# SoilMoistureSensor.net
KiCad netlist of a schematic drawn in Altium Designer
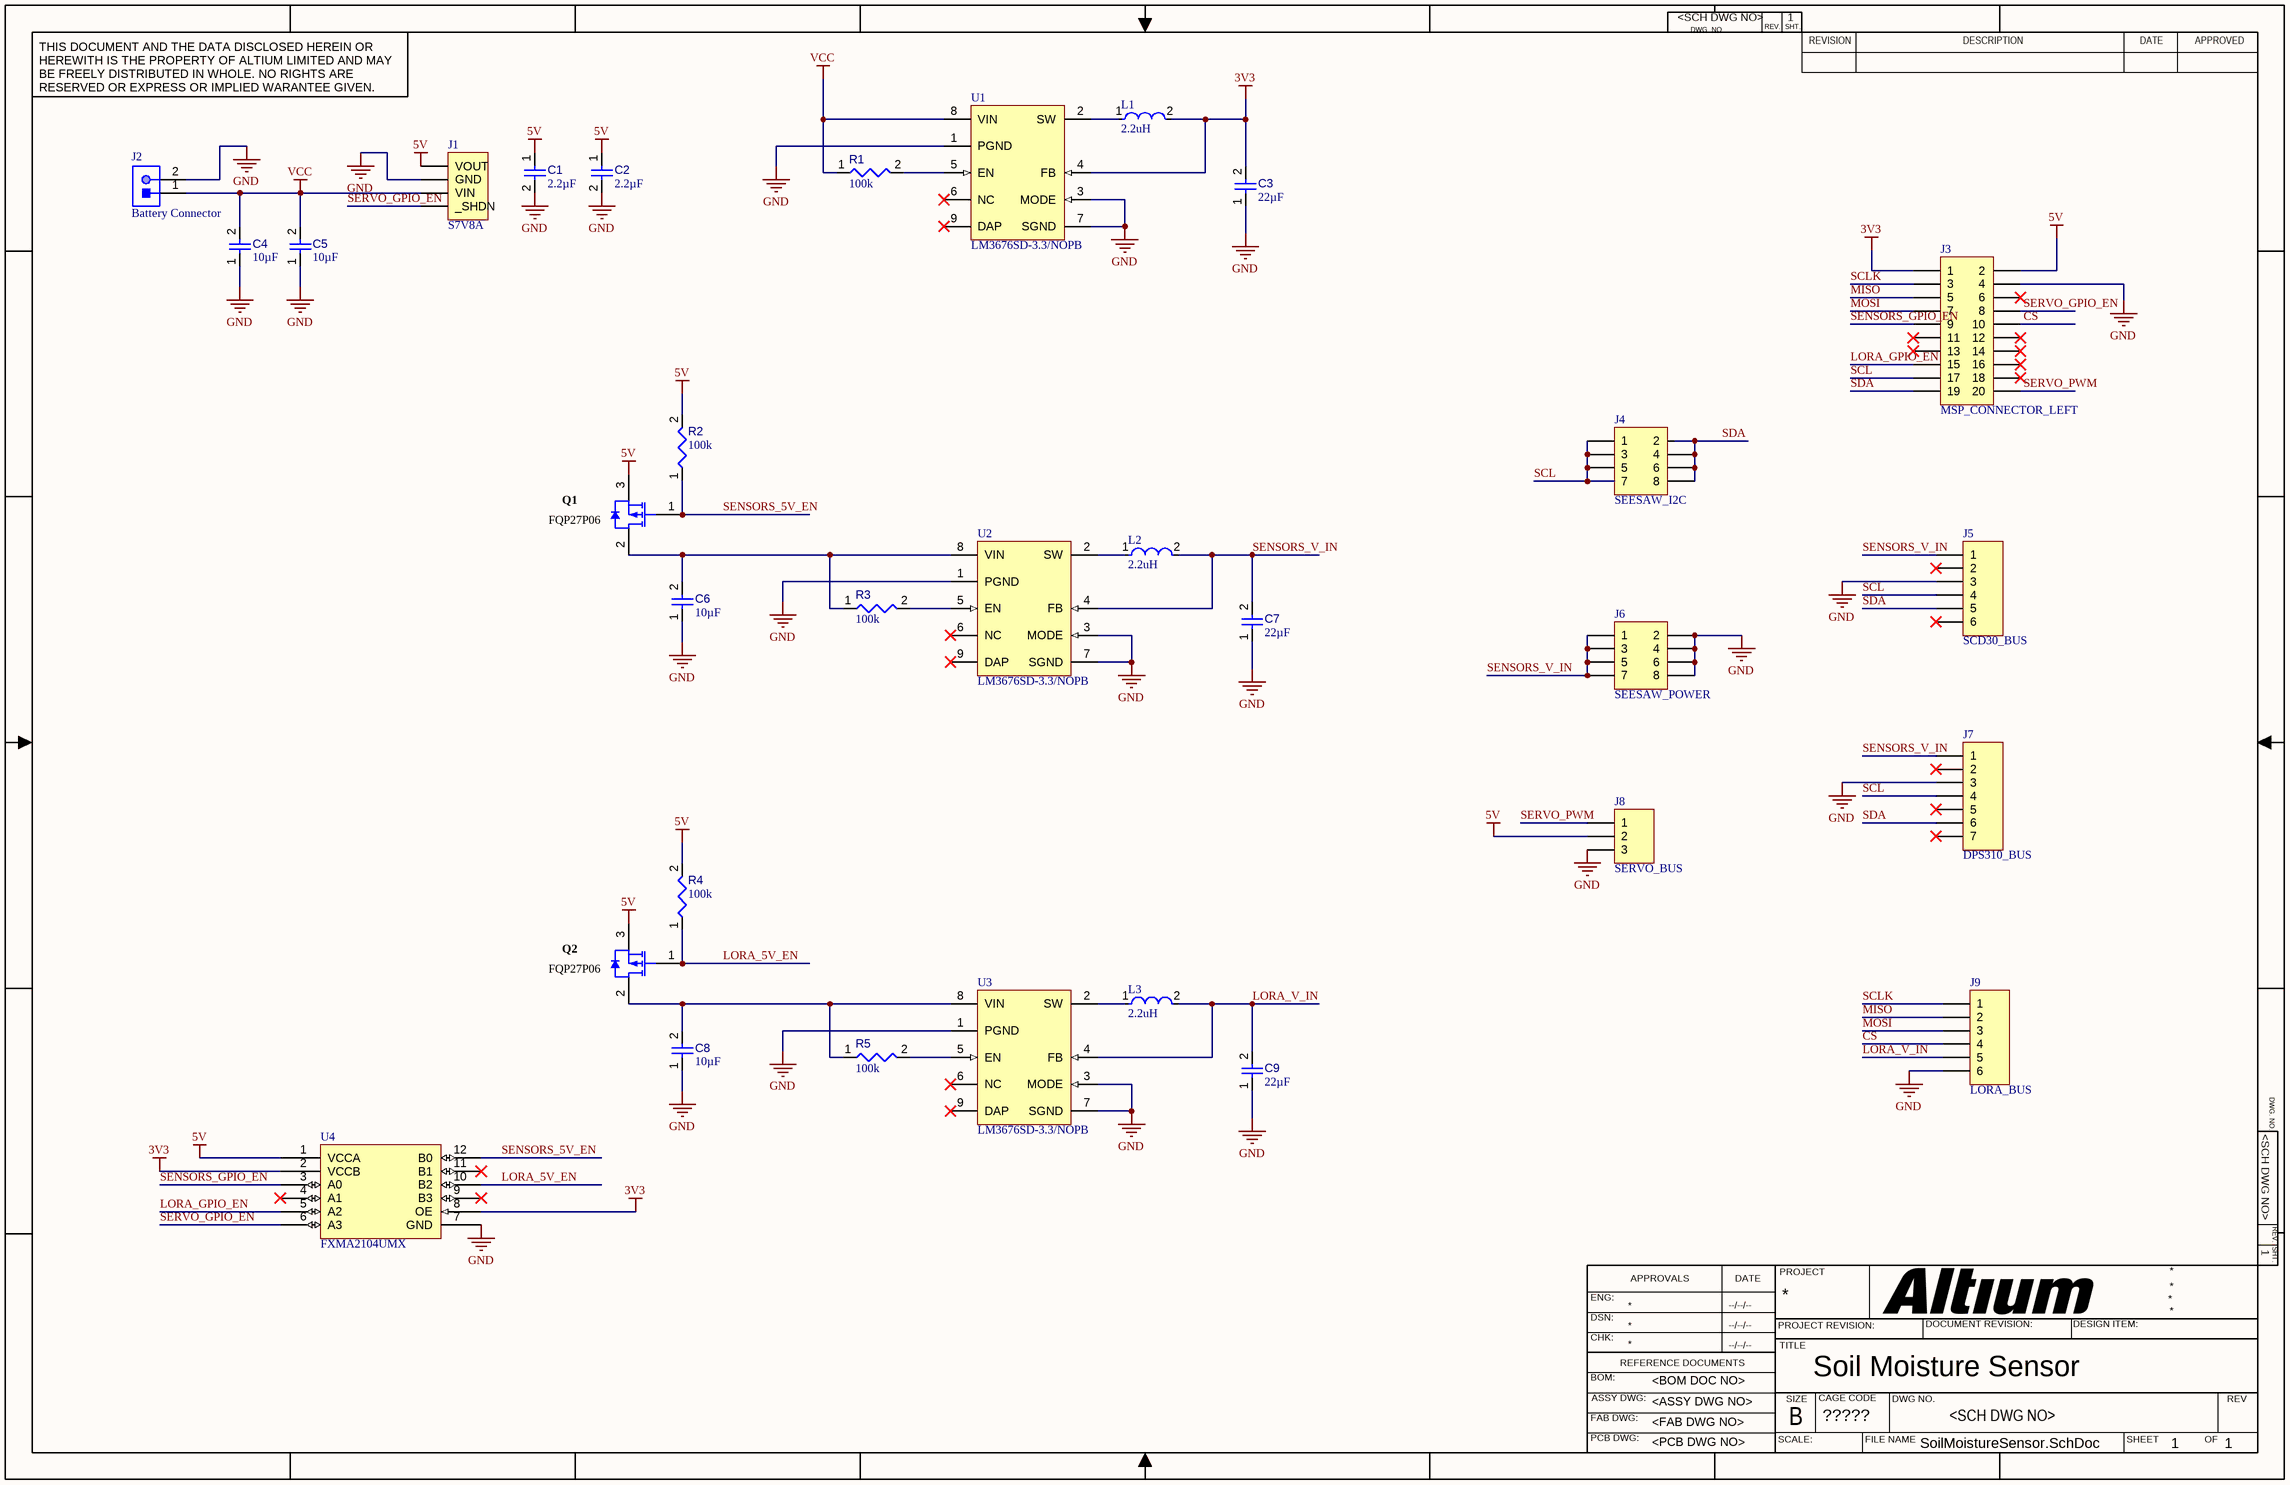
[diagram p0: SoilMoistureSensor.SchDoc]

(export (version "E")
  (design (tool "Eeschema 10.0.6"))
  (components
    (comp (ref "C1")
      (value "2.2µF")
      (footprint "CAPC0402(1005)60_L")
      (description "Chip Capacitor, 2,2µF +/-20%, 10V, 0402, Thickness 0.6 mm")
      (fields (field (name "TOLERANCE") "10%") (field (name "Comment") "Capacitor 2,2µF +/-20% 10V 0402"))
      (libsource (lib "University of Wisconsin-Madison CAE") (part "CAP-NP-2"))
    )
    (comp (ref "C2")
      (value "2.2µF")
      (footprint "CAPC0402(1005)60_L")
      (description "Chip Capacitor, 2,2µF +/-20%, 10V, 0402, Thickness 0.6 mm")
      (fields (field (name "TOLERANCE") "10%") (field (name "Comment") "Capacitor 2,2µF +/-20% 10V 0402"))
      (libsource (lib "University of Wisconsin-Madison CAE") (part "CAP-NP-2"))
    )
    (comp (ref "C3")
      (value "22µF")
      (footprint "CAPC0805(2012)145_L")
      (description "Chip Capacitor, 22µF +/-40%, 16V, 0805, Thickness 1.45 mm")
      (fields (field (name "TOLERANCE") "5%") (field (name "Comment") "Capacitor 22µF +/-40% 16V 0805"))
      (libsource (lib "University of Wisconsin-Madison CAE") (part "CAP-NP-2"))
    )
    (comp (ref "C4")
      (value "10µF")
      (footprint "CAPC0805(2012)145_L")
      (description "Chip Capacitor, 10µF +/-20%, 25V, 0805, Thickness 1.45 mm")
      (fields (field (name "TOLERANCE") "10%") (field (name "Comment") "Capacitor 10µF +/-20% 25V 0805"))
      (libsource (lib "University of Wisconsin-Madison CAE") (part "CAP-NP-2"))
    )
    (comp (ref "C5")
      (value "10µF")
      (footprint "CAPC0805(2012)145_L")
      (description "Chip Capacitor, 10µF +/-20%, 25V, 0805, Thickness 1.45 mm")
      (fields (field (name "TOLERANCE") "10%") (field (name "Comment") "Capacitor 10µF +/-20% 25V 0805"))
      (libsource (lib "University of Wisconsin-Madison CAE") (part "CAP-NP-2"))
    )
    (comp (ref "C6")
      (value "10µF")
      (footprint "CAPC0805(2012)145_L")
      (description "Chip Capacitor, 10µF +/-20%, 25V, 0805, Thickness 1.45 mm")
      (fields (field (name "TOLERANCE") "10%") (field (name "Comment") "Capacitor 10µF +/-20% 25V 0805"))
      (libsource (lib "University of Wisconsin-Madison CAE") (part "CAP-NP-2"))
    )
    (comp (ref "C7")
      (value "22µF")
      (footprint "CAPC0805(2012)145_L")
      (description "Chip Capacitor, 22µF +/-40%, 16V, 0805, Thickness 1.45 mm")
      (fields (field (name "TOLERANCE") "5%") (field (name "Comment") "Capacitor 22µF +/-40% 16V 0805"))
      (libsource (lib "University of Wisconsin-Madison CAE") (part "CAP-NP-2"))
    )
    (comp (ref "C8")
      (value "10µF")
      (footprint "CAPC0805(2012)145_L")
      (description "Chip Capacitor, 10µF +/-20%, 25V, 0805, Thickness 1.45 mm")
      (fields (field (name "TOLERANCE") "10%") (field (name "Comment") "Capacitor 10µF +/-20% 25V 0805"))
      (libsource (lib "University of Wisconsin-Madison CAE") (part "CAP-NP-2"))
    )
    (comp (ref "C9")
      (value "22µF")
      (footprint "CAPC0805(2012)145_L")
      (description "Chip Capacitor, 22µF +/-40%, 16V, 0805, Thickness 1.45 mm")
      (fields (field (name "TOLERANCE") "5%") (field (name "Comment") "Capacitor 22µF +/-40% 16V 0805"))
      (libsource (lib "University of Wisconsin-Madison CAE") (part "CAP-NP-2"))
    )
    (comp (ref "J1")
      (value "S7V8A")
      (footprint "HDR1X4")
      (description "Header, 4-Pin")
      (fields (field (name "PUBLISHER") "Altium Limited"))
      (libsource (lib "Miscellaneous Connectors") (part "Header 4"))
    )
    (comp (ref "J2")
      (value "Battery Connector")
      (footprint "JST-S2B-PH-K-S_V")
      (fields (field (name "MANUFACTURER") "Japan Solderless Terminals"))
      (libsource (lib "University of Wisconsin-Madison CAE") (part "CN-1P-M-R2"))
    )
    (comp (ref "J3")
      (value "MSP_CONNECTOR_LEFT")
      (footprint "HDR2X10")
      (description "Header, 10-Pin, Dual row")
      (fields (field (name "PUBLISHER") "Altium Limited"))
      (libsource (lib "Miscellaneous Connectors") (part "Header 10X2"))
    )
    (comp (ref "J4")
      (value "SEESAW_I2C")
      (footprint "HDR2X4")
      (description "Header, 4-Pin, Dual row")
      (fields (field (name "PUBLISHER") "Altium Limited"))
      (libsource (lib "Miscellaneous Connectors") (part "Header 4X2"))
    )
    (comp (ref "J5")
      (value "SCD30_BUS")
      (footprint "HDR1X6")
      (description "Header, 6-Pin")
      (fields (field (name "PUBLISHER") "Altium Limited"))
      (libsource (lib "Miscellaneous Connectors") (part "Header 6"))
    )
    (comp (ref "J6")
      (value "SEESAW_POWER")
      (footprint "HDR2X4")
      (description "Header, 4-Pin, Dual row")
      (fields (field (name "PUBLISHER") "Altium Limited"))
      (libsource (lib "Miscellaneous Connectors") (part "Header 4X2"))
    )
    (comp (ref "J7")
      (value "DPS310_BUS")
      (footprint "HDR1X7")
      (description "Header, 7-Pin")
      (fields (field (name "PUBLISHER") "Altium Limited"))
      (libsource (lib "Miscellaneous Connectors") (part "Header 7"))
    )
    (comp (ref "J8")
      (value "SERVO_BUS")
      (footprint "HDR1X3")
      (description "Header, 3-Pin")
      (fields (field (name "PUBLISHER") "Altium Limited"))
      (libsource (lib "Miscellaneous Connectors") (part "Header 3"))
    )
    (comp (ref "J9")
      (value "LORA_BUS")
      (footprint "HDR1X6")
      (description "Header, 6-Pin")
      (fields (field (name "PUBLISHER") "Altium Limited"))
      (libsource (lib "Miscellaneous Connectors") (part "Header 6"))
    )
    (comp (ref "L1")
      (value "2.2uH")
      (footprint "FP-NRH2412-MFG")
      (description "Shielded Wirewound Inductor 2.2uH 20% 1.19A 0.168Ω SMD")
      (fields (field (name "TOLERANCE") "20%"))
      (libsource (lib "Altium Content Vault") (part "725321dda6339637d4d059423bc1c3c"))
    )
    (comp (ref "L2")
      (value "2.2uH")
      (footprint "FP-NRH2412-MFG")
      (description "Shielded Wirewound Inductor 2.2uH 20% 1.19A 0.168Ω SMD")
      (fields (field (name "TOLERANCE") "20%"))
      (libsource (lib "Altium Content Vault") (part "725321dda6339637d4d059423bc1c3c"))
    )
    (comp (ref "L3")
      (value "2.2uH")
      (footprint "FP-NRH2412-MFG")
      (description "Shielded Wirewound Inductor 2.2uH 20% 1.19A 0.168Ω SMD")
      (fields (field (name "TOLERANCE") "20%"))
      (libsource (lib "Altium Content Vault") (part "725321dda6339637d4d059423bc1c3c"))
    )
    (comp (ref "Q1")
      (value "FQP27P06")
      (footprint "FAIR-TO-220-3")
      (description "P-Channel QFET(R) MOSFET, -60 V, -27 A, -55 to 175 degC, 3-Pin TO-220, RoHS, Tube")
      (fields (field (name "MANUFACTURER") "Fairchild"))
      (libsource (lib "Altium Content Vault") (part "PEMOS-GDS-3"))
    )
    (comp (ref "Q2")
      (value "FQP27P06")
      (footprint "FAIR-TO-220-3")
      (description "P-Channel QFET(R) MOSFET, -60 V, -27 A, -55 to 175 degC, 3-Pin TO-220, RoHS, Tube")
      (fields (field (name "MANUFACTURER") "Fairchild"))
      (libsource (lib "Altium Content Vault") (part "PEMOS-GDS-3"))
    )
    (comp (ref "R1")
      (value "100k")
      (footprint "RESC2013X70X40ML20T20")
      (description "Chip Resistor, 100 KOhm, +/- 1%, 0.125 W, -55 to 155 degC, 0805 (2012 Metric)")
      (fields (field (name "POWER") "125mW") (field (name "TOLERANCE") "1%"))
      (libsource (lib "University of Wisconsin-Madison CAE") (part "RES-2"))
    )
    (comp (ref "R2")
      (value "100k")
      (footprint "RESC2013X70X40ML20T20")
      (description "Chip Resistor, 100 KOhm, +/- 1%, 0.125 W, -55 to 155 degC, 0805 (2012 Metric)")
      (fields (field (name "POWER") "125mW") (field (name "TOLERANCE") "1%"))
      (libsource (lib "University of Wisconsin-Madison CAE") (part "RES-2"))
    )
    (comp (ref "R3")
      (value "100k")
      (footprint "RESC2013X70X40ML20T20")
      (description "Chip Resistor, 100 KOhm, +/- 1%, 0.125 W, -55 to 155 degC, 0805 (2012 Metric)")
      (fields (field (name "POWER") "125mW") (field (name "TOLERANCE") "1%"))
      (libsource (lib "University of Wisconsin-Madison CAE") (part "RES-2"))
    )
    (comp (ref "R4")
      (value "100k")
      (footprint "RESC2013X70X40ML20T20")
      (description "Chip Resistor, 100 KOhm, +/- 1%, 0.125 W, -55 to 155 degC, 0805 (2012 Metric)")
      (fields (field (name "POWER") "125mW") (field (name "TOLERANCE") "1%"))
      (libsource (lib "University of Wisconsin-Madison CAE") (part "RES-2"))
    )
    (comp (ref "R5")
      (value "100k")
      (footprint "RESC2013X70X40ML20T20")
      (description "Chip Resistor, 100 KOhm, +/- 1%, 0.125 W, -55 to 155 degC, 0805 (2012 Metric)")
      (fields (field (name "POWER") "125mW") (field (name "TOLERANCE") "1%"))
      (libsource (lib "University of Wisconsin-Madison CAE") (part "RES-2"))
    )
    (comp (ref "U1")
      (value "LM3676SD-3.3/NOPB")
      (footprint "NGQ0008A_V")
      (description "2MHz, 600mA Step-Down DC-DC Converter with Mode Control, 8-pin LLP, Pb-Free")
      (fields (field (name "MANUFACTURER") "Texas Instruments"))
      (libsource (lib "Altium Content Vault") (part "PM-DCDC-LM3676-9"))
    )
    (comp (ref "U2")
      (value "LM3676SD-3.3/NOPB")
      (footprint "NGQ0008A_V")
      (description "2MHz, 600mA Step-Down DC-DC Converter with Mode Control, 8-pin LLP, Pb-Free")
      (fields (field (name "MANUFACTURER") "Texas Instruments"))
      (libsource (lib "Altium Content Vault") (part "PM-DCDC-LM3676-9"))
    )
    (comp (ref "U3")
      (value "LM3676SD-3.3/NOPB")
      (footprint "NGQ0008A_V")
      (description "2MHz, 600mA Step-Down DC-DC Converter with Mode Control, 8-pin LLP, Pb-Free")
      (fields (field (name "MANUFACTURER") "Texas Instruments"))
      (libsource (lib "Altium Content Vault") (part "PM-DCDC-LM3676-9"))
    )
    (comp (ref "U4")
      (value "FXMA2104UMX")
      (footprint "QFN40P160X160X50-12N")
      (libsource (lib "Schlib1") (part "FXMA2104UMX"))
    )
  )
  (nets
    (net (code "1") (name "/CS") (class "Default")
      (node (ref "J3") (pin "10") (pinfunction "10_10") (pintype "passive"))
      (node (ref "J9") (pin "4") (pinfunction "4_4") (pintype "passive"))
    )
    (net (code "2") (name "/LORA_5V_EN") (class "Default")
      (node (ref "Q2") (pin "1") (pinfunction "G_1") (pintype "passive"))
      (node (ref "R4") (pin "1") (pinfunction "1_1") (pintype "passive"))
      (node (ref "U4") (pin "10") (pinfunction "B2_10") (pintype "bidirectional"))
    )
    (net (code "3") (name "/LORA_GPIO_EN") (class "Default")
      (node (ref "J3") (pin "15") (pinfunction "15_15") (pintype "passive"))
      (node (ref "U4") (pin "5") (pinfunction "A2_5") (pintype "bidirectional"))
    )
    (net (code "4") (name "/LORA_V_IN") (class "Default")
      (node (ref "C9") (pin "2") (pinfunction "2_2") (pintype "passive"))
      (node (ref "J9") (pin "5") (pinfunction "5_5") (pintype "passive"))
      (node (ref "L3") (pin "2") (pinfunction "2_2") (pintype "passive"))
      (node (ref "U3") (pin "4") (pinfunction "FB_4") (pintype "input"))
    )
    (net (code "5") (name "/MISO") (class "Default")
      (node (ref "J3") (pin "5") (pinfunction "5_5") (pintype "passive"))
      (node (ref "J9") (pin "2") (pinfunction "2_2") (pintype "passive"))
    )
    (net (code "6") (name "/MOSI") (class "Default")
      (node (ref "J3") (pin "7") (pinfunction "7_7") (pintype "passive"))
      (node (ref "J9") (pin "3") (pinfunction "3_3") (pintype "passive"))
    )
    (net (code "7") (name "/SCL") (class "Default")
      (node (ref "J3") (pin "17") (pinfunction "17_17") (pintype "passive"))
      (node (ref "J4") (pin "1") (pinfunction "1_1") (pintype "passive"))
      (node (ref "J4") (pin "3") (pinfunction "3_3") (pintype "passive"))
      (node (ref "J4") (pin "5") (pinfunction "5_5") (pintype "passive"))
      (node (ref "J4") (pin "7") (pinfunction "7_7") (pintype "passive"))
      (node (ref "J5") (pin "4") (pinfunction "4_4") (pintype "passive"))
      (node (ref "J7") (pin "4") (pinfunction "4_4") (pintype "passive"))
    )
    (net (code "8") (name "/SCLK") (class "Default")
      (node (ref "J3") (pin "3") (pinfunction "3_3") (pintype "passive"))
      (node (ref "J9") (pin "1") (pinfunction "1_1") (pintype "passive"))
    )
    (net (code "9") (name "/SDA") (class "Default")
      (node (ref "J3") (pin "19") (pinfunction "19_19") (pintype "passive"))
      (node (ref "J4") (pin "2") (pinfunction "2_2") (pintype "passive"))
      (node (ref "J4") (pin "4") (pinfunction "4_4") (pintype "passive"))
      (node (ref "J4") (pin "6") (pinfunction "6_6") (pintype "passive"))
      (node (ref "J4") (pin "8") (pinfunction "8_8") (pintype "passive"))
      (node (ref "J5") (pin "5") (pinfunction "5_5") (pintype "passive"))
      (node (ref "J7") (pin "6") (pinfunction "6_6") (pintype "passive"))
    )
    (net (code "10") (name "/SENSORS_5V_EN") (class "Default")
      (node (ref "Q1") (pin "1") (pinfunction "G_1") (pintype "passive"))
      (node (ref "R2") (pin "1") (pinfunction "1_1") (pintype "passive"))
      (node (ref "U4") (pin "12") (pinfunction "B0_12") (pintype "bidirectional"))
    )
    (net (code "11") (name "/SENSORS_GPIO_EN") (class "Default")
      (node (ref "J3") (pin "9") (pinfunction "9_9") (pintype "passive"))
      (node (ref "U4") (pin "3") (pinfunction "A0_3") (pintype "bidirectional"))
    )
    (net (code "12") (name "/SENSORS_V_IN") (class "Default")
      (node (ref "C7") (pin "2") (pinfunction "2_2") (pintype "passive"))
      (node (ref "J5") (pin "1") (pinfunction "1_1") (pintype "passive"))
      (node (ref "J6") (pin "1") (pinfunction "1_1") (pintype "passive"))
      (node (ref "J6") (pin "3") (pinfunction "3_3") (pintype "passive"))
      (node (ref "J6") (pin "5") (pinfunction "5_5") (pintype "passive"))
      (node (ref "J6") (pin "7") (pinfunction "7_7") (pintype "passive"))
      (node (ref "J7") (pin "1") (pinfunction "1_1") (pintype "passive"))
      (node (ref "L2") (pin "2") (pinfunction "2_2") (pintype "passive"))
      (node (ref "U2") (pin "4") (pinfunction "FB_4") (pintype "input"))
    )
    (net (code "13") (name "/SERVO_GPIO_EN") (class "Default")
      (node (ref "J1") (pin "4") (pinfunction "_SHDN_4") (pintype "passive"))
      (node (ref "J3") (pin "8") (pinfunction "8_8") (pintype "passive"))
      (node (ref "U4") (pin "6") (pinfunction "A3_6") (pintype "bidirectional"))
    )
    (net (code "14") (name "/SERVO_PWM") (class "Default")
      (node (ref "J3") (pin "20") (pinfunction "20_20") (pintype "passive"))
      (node (ref "J8") (pin "1") (pinfunction "1_1") (pintype "passive"))
    )
    (net (code "15") (name "3V3") (class "Default")
      (node (ref "C3") (pin "2") (pinfunction "2_2") (pintype "passive"))
      (node (ref "J3") (pin "1") (pinfunction "1_1") (pintype "passive"))
      (node (ref "L1") (pin "2") (pinfunction "2_2") (pintype "passive"))
      (node (ref "U1") (pin "4") (pinfunction "FB_4") (pintype "input"))
      (node (ref "U4") (pin "2") (pinfunction "VCCB_2") (pintype "power_in"))
      (node (ref "U4") (pin "8") (pinfunction "OE_8") (pintype "input"))
    )
    (net (code "16") (name "5V") (class "Default")
      (node (ref "C1") (pin "1") (pinfunction "1_1") (pintype "passive"))
      (node (ref "C2") (pin "1") (pinfunction "1_1") (pintype "passive"))
      (node (ref "J1") (pin "1") (pinfunction "VOUT_1") (pintype "passive"))
      (node (ref "J3") (pin "2") (pinfunction "2_2") (pintype "passive"))
      (node (ref "J8") (pin "2") (pinfunction "2_2") (pintype "passive"))
      (node (ref "Q1") (pin "3") (pinfunction "S_3") (pintype "passive"))
      (node (ref "Q2") (pin "3") (pinfunction "S_3") (pintype "passive"))
      (node (ref "R2") (pin "2") (pinfunction "2_2") (pintype "passive"))
      (node (ref "R4") (pin "2") (pinfunction "2_2") (pintype "passive"))
      (node (ref "U4") (pin "1") (pinfunction "VCCA_1") (pintype "power_in"))
    )
    (net (code "17") (name "GND") (class "Default")
      (node (ref "C1") (pin "2") (pinfunction "2_2") (pintype "passive"))
      (node (ref "C2") (pin "2") (pinfunction "2_2") (pintype "passive"))
      (node (ref "C3") (pin "1") (pinfunction "1_1") (pintype "passive"))
      (node (ref "C4") (pin "1") (pinfunction "1_1") (pintype "passive"))
      (node (ref "C5") (pin "1") (pinfunction "1_1") (pintype "passive"))
      (node (ref "C6") (pin "1") (pinfunction "1_1") (pintype "passive"))
      (node (ref "C7") (pin "1") (pinfunction "1_1") (pintype "passive"))
      (node (ref "C8") (pin "1") (pinfunction "1_1") (pintype "passive"))
      (node (ref "C9") (pin "1") (pinfunction "1_1") (pintype "passive"))
      (node (ref "J1") (pin "2") (pinfunction "GND_2") (pintype "passive"))
      (node (ref "J2") (pin "2") (pinfunction "2_2") (pintype "passive"))
      (node (ref "J3") (pin "4") (pinfunction "4_4") (pintype "passive"))
      (node (ref "J5") (pin "3") (pinfunction "3_3") (pintype "passive"))
      (node (ref "J6") (pin "2") (pinfunction "2_2") (pintype "passive"))
      (node (ref "J6") (pin "4") (pinfunction "4_4") (pintype "passive"))
      (node (ref "J6") (pin "6") (pinfunction "6_6") (pintype "passive"))
      (node (ref "J6") (pin "8") (pinfunction "8_8") (pintype "passive"))
      (node (ref "J7") (pin "3") (pinfunction "3_3") (pintype "passive"))
      (node (ref "J8") (pin "3") (pinfunction "3_3") (pintype "passive"))
      (node (ref "J9") (pin "6") (pinfunction "6_6") (pintype "passive"))
      (node (ref "U1") (pin "1") (pinfunction "PGND_1") (pintype "power_in"))
      (node (ref "U1") (pin "3") (pinfunction "MODE_3") (pintype "input"))
      (node (ref "U1") (pin "7") (pinfunction "SGND_7") (pintype "power_in"))
      (node (ref "U2") (pin "1") (pinfunction "PGND_1") (pintype "power_in"))
      (node (ref "U2") (pin "3") (pinfunction "MODE_3") (pintype "input"))
      (node (ref "U2") (pin "7") (pinfunction "SGND_7") (pintype "power_in"))
      (node (ref "U3") (pin "1") (pinfunction "PGND_1") (pintype "power_in"))
      (node (ref "U3") (pin "3") (pinfunction "MODE_3") (pintype "input"))
      (node (ref "U3") (pin "7") (pinfunction "SGND_7") (pintype "power_in"))
      (node (ref "U4") (pin "7") (pinfunction "GND_7") (pintype "power_in"))
    )
    (net (code "18") (name "Net-(Q1-D)") (class "Default")
      (node (ref "C6") (pin "2") (pinfunction "2_2") (pintype "passive"))
      (node (ref "Q1") (pin "2") (pinfunction "D_2") (pintype "passive"))
      (node (ref "R3") (pin "1") (pinfunction "1_1") (pintype "passive"))
      (node (ref "U2") (pin "8") (pinfunction "VIN_8") (pintype "power_in"))
    )
    (net (code "19") (name "Net-(Q2-D)") (class "Default")
      (node (ref "C8") (pin "2") (pinfunction "2_2") (pintype "passive"))
      (node (ref "Q2") (pin "2") (pinfunction "D_2") (pintype "passive"))
      (node (ref "R5") (pin "1") (pinfunction "1_1") (pintype "passive"))
      (node (ref "U3") (pin "8") (pinfunction "VIN_8") (pintype "power_in"))
    )
    (net (code "20") (name "Net-(U1-EN)") (class "Default")
      (node (ref "R1") (pin "2") (pinfunction "2_2") (pintype "passive"))
      (node (ref "U1") (pin "5") (pinfunction "EN_5") (pintype "input"))
    )
    (net (code "21") (name "Net-(U1-SW)") (class "Default")
      (node (ref "L1") (pin "1") (pinfunction "1_1") (pintype "passive"))
      (node (ref "U1") (pin "2") (pinfunction "SW_2") (pintype "power_in"))
    )
    (net (code "22") (name "Net-(U2-EN)") (class "Default")
      (node (ref "R3") (pin "2") (pinfunction "2_2") (pintype "passive"))
      (node (ref "U2") (pin "5") (pinfunction "EN_5") (pintype "input"))
    )
    (net (code "23") (name "Net-(U2-SW)") (class "Default")
      (node (ref "L2") (pin "1") (pinfunction "1_1") (pintype "passive"))
      (node (ref "U2") (pin "2") (pinfunction "SW_2") (pintype "power_in"))
    )
    (net (code "24") (name "Net-(U3-EN)") (class "Default")
      (node (ref "R5") (pin "2") (pinfunction "2_2") (pintype "passive"))
      (node (ref "U3") (pin "5") (pinfunction "EN_5") (pintype "input"))
    )
    (net (code "25") (name "Net-(U3-SW)") (class "Default")
      (node (ref "L3") (pin "1") (pinfunction "1_1") (pintype "passive"))
      (node (ref "U3") (pin "2") (pinfunction "SW_2") (pintype "power_in"))
    )
    (net (code "26") (name "VCC") (class "Default")
      (node (ref "C4") (pin "2") (pinfunction "2_2") (pintype "passive"))
      (node (ref "C5") (pin "2") (pinfunction "2_2") (pintype "passive"))
      (node (ref "J1") (pin "3") (pinfunction "VIN_3") (pintype "passive"))
      (node (ref "J2") (pin "1") (pinfunction "1_1") (pintype "passive"))
      (node (ref "R1") (pin "1") (pinfunction "1_1") (pintype "passive"))
      (node (ref "U1") (pin "8") (pinfunction "VIN_8") (pintype "power_in"))
    )
    (net (code "27") (name "unconnected-(J3-Pad6)") (class "Default")
      (node (ref "J3") (pin "6") (pinfunction "6_6") (pintype "passive+no_connect"))
    )
    (net (code "28") (name "unconnected-(J3-Pad11)") (class "Default")
      (node (ref "J3") (pin "11") (pinfunction "11_11") (pintype "passive+no_connect"))
    )
    (net (code "29") (name "unconnected-(J3-Pad12)") (class "Default")
      (node (ref "J3") (pin "12") (pinfunction "12_12") (pintype "passive+no_connect"))
    )
    (net (code "30") (name "unconnected-(J3-Pad13)") (class "Default")
      (node (ref "J3") (pin "13") (pinfunction "13_13") (pintype "passive+no_connect"))
    )
    (net (code "31") (name "unconnected-(J3-Pad14)") (class "Default")
      (node (ref "J3") (pin "14") (pinfunction "14_14") (pintype "passive+no_connect"))
    )
    (net (code "32") (name "unconnected-(J3-Pad16)") (class "Default")
      (node (ref "J3") (pin "16") (pinfunction "16_16") (pintype "passive+no_connect"))
    )
    (net (code "33") (name "unconnected-(J3-Pad18)") (class "Default")
      (node (ref "J3") (pin "18") (pinfunction "18_18") (pintype "passive+no_connect"))
    )
    (net (code "34") (name "unconnected-(J5-Pad2)") (class "Default")
      (node (ref "J5") (pin "2") (pinfunction "2_2") (pintype "passive+no_connect"))
    )
    (net (code "35") (name "unconnected-(J5-Pad6)") (class "Default")
      (node (ref "J5") (pin "6") (pinfunction "6_6") (pintype "passive+no_connect"))
    )
    (net (code "36") (name "unconnected-(J7-Pad2)") (class "Default")
      (node (ref "J7") (pin "2") (pinfunction "2_2") (pintype "passive+no_connect"))
    )
    (net (code "37") (name "unconnected-(J7-Pad5)") (class "Default")
      (node (ref "J7") (pin "5") (pinfunction "5_5") (pintype "passive+no_connect"))
    )
    (net (code "38") (name "unconnected-(J7-Pad7)") (class "Default")
      (node (ref "J7") (pin "7") (pinfunction "7_7") (pintype "passive+no_connect"))
    )
    (net (code "39") (name "unconnected-(U1-DAP-Pad9)") (class "Default")
      (node (ref "U1") (pin "9") (pinfunction "DAP_9") (pintype "power_in+no_connect"))
    )
    (net (code "40") (name "unconnected-(U1-NC-Pad6)") (class "Default")
      (node (ref "U1") (pin "6") (pinfunction "NC_6") (pintype "passive+no_connect"))
    )
    (net (code "41") (name "unconnected-(U2-DAP-Pad9)") (class "Default")
      (node (ref "U2") (pin "9") (pinfunction "DAP_9") (pintype "power_in+no_connect"))
    )
    (net (code "42") (name "unconnected-(U2-NC-Pad6)") (class "Default")
      (node (ref "U2") (pin "6") (pinfunction "NC_6") (pintype "passive+no_connect"))
    )
    (net (code "43") (name "unconnected-(U3-DAP-Pad9)") (class "Default")
      (node (ref "U3") (pin "9") (pinfunction "DAP_9") (pintype "power_in+no_connect"))
    )
    (net (code "44") (name "unconnected-(U3-NC-Pad6)") (class "Default")
      (node (ref "U3") (pin "6") (pinfunction "NC_6") (pintype "passive+no_connect"))
    )
    (net (code "45") (name "unconnected-(U4-A1-Pad4)") (class "Default")
      (node (ref "U4") (pin "4") (pinfunction "A1_4") (pintype "bidirectional+no_connect"))
    )
    (net (code "46") (name "unconnected-(U4-B1-Pad11)") (class "Default")
      (node (ref "U4") (pin "11") (pinfunction "B1_11") (pintype "bidirectional+no_connect"))
    )
    (net (code "47") (name "unconnected-(U4-B3-Pad9)") (class "Default")
      (node (ref "U4") (pin "9") (pinfunction "B3_9") (pintype "bidirectional+no_connect"))
    )
  )
)
